# M624X.net
KiCad netlist of a schematic drawn in EAGLE
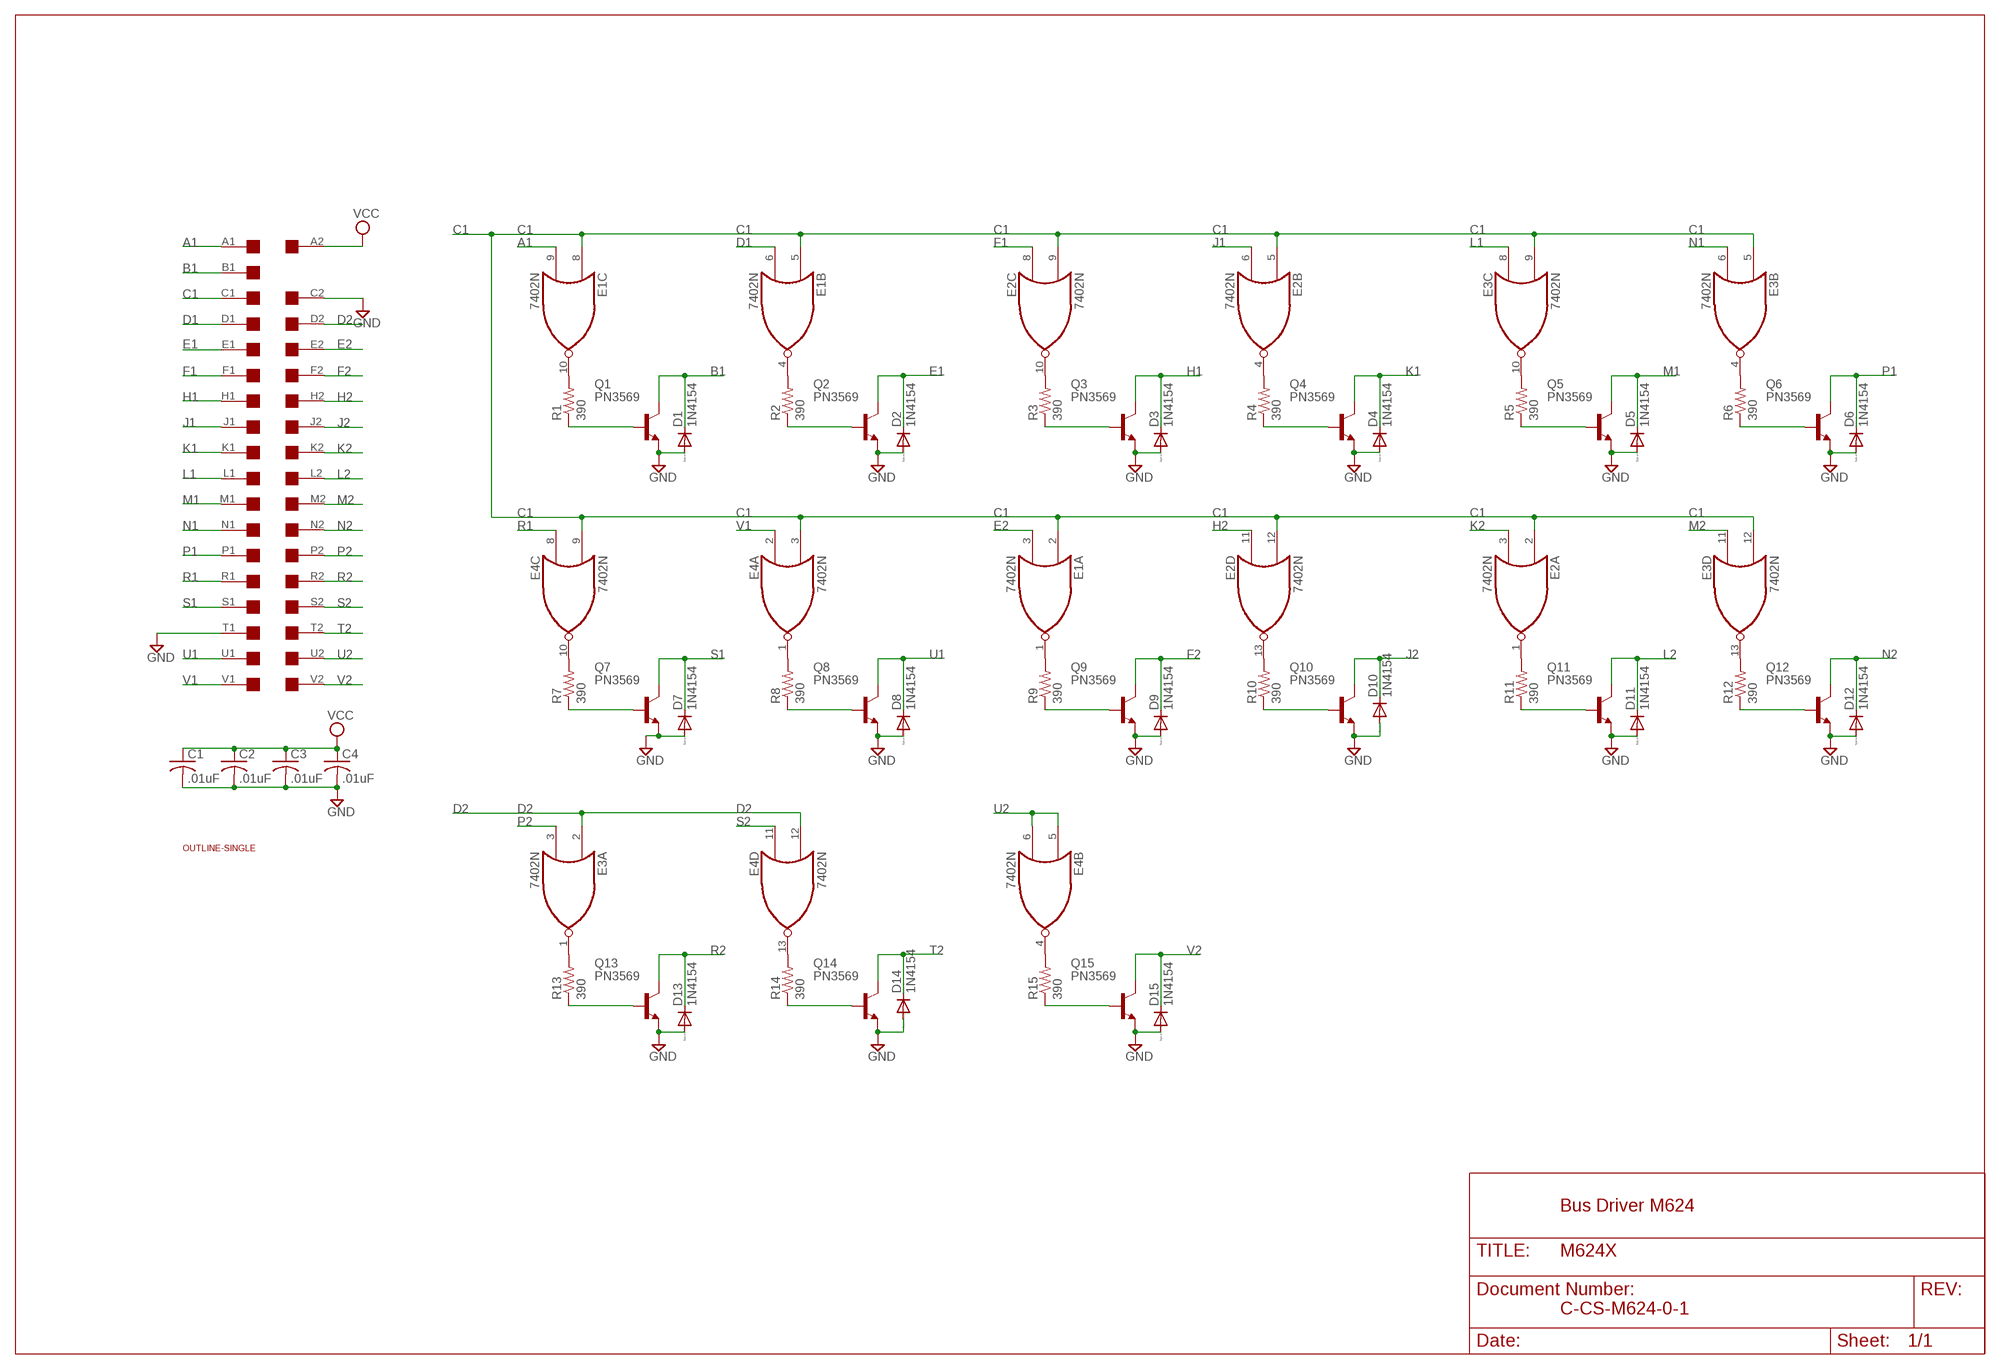
[diagram p0: schematic, sheet 1]

(export (version "E")
  (design (tool "Eeschema 10.0.6"))
  (components
    (comp (ref "C1")
      (value ".01uF")
      (footprint "eagle-import:C050-025X075")
      (libsource (lib "eagle-import") (part "C-US050-025X075"))
    )
    (comp (ref "C2")
      (value ".01uF")
      (footprint "eagle-import:C050-025X075")
      (libsource (lib "eagle-import") (part "C-US050-025X075"))
    )
    (comp (ref "C3")
      (value ".01uF")
      (footprint "eagle-import:C050-025X075")
      (libsource (lib "eagle-import") (part "C-US050-025X075"))
    )
    (comp (ref "C4")
      (value ".01uF")
      (footprint "eagle-import:C050-025X075")
      (libsource (lib "eagle-import") (part "C-US050-025X075"))
    )
    (comp (ref "D1")
      (value "1N4154")
      (footprint "eagle-import:DO35-10")
      (libsource (lib "eagle-import") (part "1N4148DO35-10"))
    )
    (comp (ref "D2")
      (value "1N4154")
      (footprint "eagle-import:DO35-10")
      (libsource (lib "eagle-import") (part "1N4148DO35-10"))
    )
    (comp (ref "D3")
      (value "1N4154")
      (footprint "eagle-import:DO35-10")
      (libsource (lib "eagle-import") (part "1N4148DO35-10"))
    )
    (comp (ref "D4")
      (value "1N4154")
      (footprint "eagle-import:DO35-10")
      (libsource (lib "eagle-import") (part "1N4148DO35-10"))
    )
    (comp (ref "D5")
      (value "1N4154")
      (footprint "eagle-import:DO35-10")
      (libsource (lib "eagle-import") (part "1N4148DO35-10"))
    )
    (comp (ref "D6")
      (value "1N4154")
      (footprint "eagle-import:DO35-10")
      (libsource (lib "eagle-import") (part "1N4148DO35-10"))
    )
    (comp (ref "D7")
      (value "1N4154")
      (footprint "eagle-import:DO35-10")
      (libsource (lib "eagle-import") (part "1N4148DO35-10"))
    )
    (comp (ref "D8")
      (value "1N4154")
      (footprint "eagle-import:DO35-10")
      (libsource (lib "eagle-import") (part "1N4148DO35-10"))
    )
    (comp (ref "D9")
      (value "1N4154")
      (footprint "eagle-import:DO35-10")
      (libsource (lib "eagle-import") (part "1N4148DO35-10"))
    )
    (comp (ref "D10")
      (value "1N4154")
      (footprint "eagle-import:DO35-10")
      (libsource (lib "eagle-import") (part "1N4148DO35-10"))
    )
    (comp (ref "D11")
      (value "1N4154")
      (footprint "eagle-import:DO35-10")
      (libsource (lib "eagle-import") (part "1N4148DO35-10"))
    )
    (comp (ref "D12")
      (value "1N4154")
      (footprint "eagle-import:DO35-10")
      (libsource (lib "eagle-import") (part "1N4148DO35-10"))
    )
    (comp (ref "D13")
      (value "1N4154")
      (footprint "eagle-import:DO35-10")
      (libsource (lib "eagle-import") (part "1N4148DO35-10"))
    )
    (comp (ref "D14")
      (value "1N4154")
      (footprint "eagle-import:DO35-10")
      (libsource (lib "eagle-import") (part "1N4148DO35-10"))
    )
    (comp (ref "D15")
      (value "1N4154")
      (footprint "eagle-import:DO35-10")
      (libsource (lib "eagle-import") (part "1N4148DO35-10"))
    )
    (comp (ref "E1")
      (value "7402N")
      (footprint "eagle-import:DIL14")
      (libsource (lib "eagle-import") (part "7402N"))
    )
    (comp (ref "E2")
      (value "7402N")
      (footprint "eagle-import:DIL14")
      (libsource (lib "eagle-import") (part "7402N"))
    )
    (comp (ref "E3")
      (value "7402N")
      (footprint "eagle-import:DIL14")
      (libsource (lib "eagle-import") (part "7402N"))
    )
    (comp (ref "E4")
      (value "7402N")
      (footprint "eagle-import:DIL14")
      (libsource (lib "eagle-import") (part "7402N"))
    )
    (comp (ref "Q1")
      (value "PN3569")
      (footprint "eagle-import:TO39")
      (libsource (lib "eagle-import") (part "-NPN-TO39-EBC2N1613"))
    )
    (comp (ref "Q2")
      (value "PN3569")
      (footprint "eagle-import:TO39")
      (libsource (lib "eagle-import") (part "-NPN-TO39-EBC2N1613"))
    )
    (comp (ref "Q3")
      (value "PN3569")
      (footprint "eagle-import:TO39")
      (libsource (lib "eagle-import") (part "-NPN-TO39-EBC2N1613"))
    )
    (comp (ref "Q4")
      (value "PN3569")
      (footprint "eagle-import:TO39")
      (libsource (lib "eagle-import") (part "-NPN-TO39-EBC2N1613"))
    )
    (comp (ref "Q5")
      (value "PN3569")
      (footprint "eagle-import:TO39")
      (libsource (lib "eagle-import") (part "-NPN-TO39-EBC2N1613"))
    )
    (comp (ref "Q6")
      (value "PN3569")
      (footprint "eagle-import:TO39")
      (libsource (lib "eagle-import") (part "-NPN-TO39-EBC2N1613"))
    )
    (comp (ref "Q7")
      (value "PN3569")
      (footprint "eagle-import:TO39")
      (libsource (lib "eagle-import") (part "-NPN-TO39-EBC2N1613"))
    )
    (comp (ref "Q8")
      (value "PN3569")
      (footprint "eagle-import:TO39")
      (libsource (lib "eagle-import") (part "-NPN-TO39-EBC2N1613"))
    )
    (comp (ref "Q9")
      (value "PN3569")
      (footprint "eagle-import:TO39")
      (libsource (lib "eagle-import") (part "-NPN-TO39-EBC2N1613"))
    )
    (comp (ref "Q10")
      (value "PN3569")
      (footprint "eagle-import:TO39")
      (libsource (lib "eagle-import") (part "-NPN-TO39-EBC2N1613"))
    )
    (comp (ref "Q11")
      (value "PN3569")
      (footprint "eagle-import:TO39")
      (libsource (lib "eagle-import") (part "-NPN-TO39-EBC2N1613"))
    )
    (comp (ref "Q12")
      (value "PN3569")
      (footprint "eagle-import:TO39")
      (libsource (lib "eagle-import") (part "-NPN-TO39-EBC2N1613"))
    )
    (comp (ref "Q13")
      (value "PN3569")
      (footprint "eagle-import:TO39")
      (libsource (lib "eagle-import") (part "-NPN-TO39-EBC2N1613"))
    )
    (comp (ref "Q14")
      (value "PN3569")
      (footprint "eagle-import:TO39")
      (libsource (lib "eagle-import") (part "-NPN-TO39-EBC2N1613"))
    )
    (comp (ref "Q15")
      (value "PN3569")
      (footprint "eagle-import:TO39")
      (libsource (lib "eagle-import") (part "-NPN-TO39-EBC2N1613"))
    )
    (comp (ref "R1")
      (value "390")
      (footprint "eagle-import:0207_10")
      (libsource (lib "eagle-import") (part "R-US_0207/10"))
    )
    (comp (ref "R2")
      (value "390")
      (footprint "eagle-import:0207_10")
      (libsource (lib "eagle-import") (part "R-US_0207/10"))
    )
    (comp (ref "R3")
      (value "390")
      (footprint "eagle-import:0207_10")
      (libsource (lib "eagle-import") (part "R-US_0207/10"))
    )
    (comp (ref "R4")
      (value "390")
      (footprint "eagle-import:0207_10")
      (libsource (lib "eagle-import") (part "R-US_0207/10"))
    )
    (comp (ref "R5")
      (value "390")
      (footprint "eagle-import:0207_10")
      (libsource (lib "eagle-import") (part "R-US_0207/10"))
    )
    (comp (ref "R6")
      (value "390")
      (footprint "eagle-import:0207_10")
      (libsource (lib "eagle-import") (part "R-US_0207/10"))
    )
    (comp (ref "R7")
      (value "390")
      (footprint "eagle-import:0207_10")
      (libsource (lib "eagle-import") (part "R-US_0207/10"))
    )
    (comp (ref "R8")
      (value "390")
      (footprint "eagle-import:0207_10")
      (libsource (lib "eagle-import") (part "R-US_0207/10"))
    )
    (comp (ref "R9")
      (value "390")
      (footprint "eagle-import:0207_10")
      (libsource (lib "eagle-import") (part "R-US_0207/10"))
    )
    (comp (ref "R10")
      (value "390")
      (footprint "eagle-import:0207_10")
      (libsource (lib "eagle-import") (part "R-US_0207/10"))
    )
    (comp (ref "R11")
      (value "390")
      (footprint "eagle-import:0207_10")
      (libsource (lib "eagle-import") (part "R-US_0207/10"))
    )
    (comp (ref "R12")
      (value "390")
      (footprint "eagle-import:0207_10")
      (libsource (lib "eagle-import") (part "R-US_0207/10"))
    )
    (comp (ref "R13")
      (value "390")
      (footprint "eagle-import:0207_10")
      (libsource (lib "eagle-import") (part "R-US_0207/10"))
    )
    (comp (ref "R14")
      (value "390")
      (footprint "eagle-import:0207_10")
      (libsource (lib "eagle-import") (part "R-US_0207/10"))
    )
    (comp (ref "R15")
      (value "390")
      (footprint "eagle-import:0207_10")
      (libsource (lib "eagle-import") (part "R-US_0207/10"))
    )
    (comp (ref "U$1")
      (value "OUTLINE-SINGLE")
      (footprint "eagle-import:SINGLE")
      (libsource (lib "eagle-import") (part "OUTLINE-SINGLE"))
    )
    (comp (ref "U$4")
      (value "SINGLE")
      (footprint "eagle-import:EDGE-CON2")
      (libsource (lib "eagle-import") (part "SINGLE"))
    )
  )
  (nets
    (net (code "1") (name "/A1") (class "Default")
      (node (ref "E1") (pin "9") (pinfunction "I1_9") (pintype "input"))
      (node (ref "U$4") (pin "A1") (pinfunction "1_A1") (pintype "bidirectional"))
    )
    (net (code "2") (name "/B1") (class "Default")
      (node (ref "D1") (pin "C") (pinfunction "C_C") (pintype "passive"))
      (node (ref "Q1") (pin "3") (pinfunction "C_3") (pintype "passive"))
      (node (ref "U$4") (pin "B1") (pinfunction "1_B1") (pintype "bidirectional"))
    )
    (net (code "3") (name "/C1") (class "Default")
      (node (ref "E1") (pin "2") (pinfunction "I0_2") (pintype "input"))
      (node (ref "E1") (pin "5") (pinfunction "I0_5") (pintype "input"))
      (node (ref "E1") (pin "8") (pinfunction "I0_8") (pintype "input"))
      (node (ref "E2") (pin "12") (pinfunction "I1_12") (pintype "input"))
      (node (ref "E2") (pin "2") (pinfunction "I0_2") (pintype "input"))
      (node (ref "E2") (pin "5") (pinfunction "I0_5") (pintype "input"))
      (node (ref "E2") (pin "9") (pinfunction "I1_9") (pintype "input"))
      (node (ref "E3") (pin "12") (pinfunction "I1_12") (pintype "input"))
      (node (ref "E3") (pin "5") (pinfunction "I0_5") (pintype "input"))
      (node (ref "E3") (pin "9") (pinfunction "I1_9") (pintype "input"))
      (node (ref "E4") (pin "3") (pinfunction "I1_3") (pintype "input"))
      (node (ref "E4") (pin "9") (pinfunction "I1_9") (pintype "input"))
      (node (ref "U$4") (pin "C1") (pinfunction "1_C1") (pintype "bidirectional"))
    )
    (net (code "4") (name "/D1") (class "Default")
      (node (ref "E1") (pin "6") (pinfunction "I1_6") (pintype "input"))
      (node (ref "U$4") (pin "D1") (pinfunction "1_D1") (pintype "bidirectional"))
    )
    (net (code "5") (name "/D2") (class "Default")
      (node (ref "E3") (pin "2") (pinfunction "I0_2") (pintype "input"))
      (node (ref "E4") (pin "12") (pinfunction "I1_12") (pintype "input"))
      (node (ref "U$4") (pin "D2") (pinfunction "1_D2") (pintype "bidirectional"))
    )
    (net (code "6") (name "/E1") (class "Default")
      (node (ref "D2") (pin "C") (pinfunction "C_C") (pintype "passive"))
      (node (ref "Q2") (pin "3") (pinfunction "C_3") (pintype "passive"))
      (node (ref "U$4") (pin "E1") (pinfunction "1_E1") (pintype "bidirectional"))
    )
    (net (code "7") (name "/E2") (class "Default")
      (node (ref "E1") (pin "3") (pinfunction "I1_3") (pintype "input"))
      (node (ref "U$4") (pin "E2") (pinfunction "1_E2") (pintype "bidirectional"))
    )
    (net (code "8") (name "/F1") (class "Default")
      (node (ref "E2") (pin "8") (pinfunction "I0_8") (pintype "input"))
      (node (ref "U$4") (pin "F1") (pinfunction "1_F1") (pintype "bidirectional"))
    )
    (net (code "9") (name "/F2") (class "Default")
      (node (ref "D9") (pin "C") (pinfunction "C_C") (pintype "passive"))
      (node (ref "Q9") (pin "3") (pinfunction "C_3") (pintype "passive"))
      (node (ref "U$4") (pin "F2") (pinfunction "1_F2") (pintype "bidirectional"))
    )
    (net (code "10") (name "/H1") (class "Default")
      (node (ref "D3") (pin "C") (pinfunction "C_C") (pintype "passive"))
      (node (ref "Q3") (pin "3") (pinfunction "C_3") (pintype "passive"))
      (node (ref "U$4") (pin "H1") (pinfunction "1_H1") (pintype "bidirectional"))
    )
    (net (code "11") (name "/H2") (class "Default")
      (node (ref "E2") (pin "11") (pinfunction "I0_11") (pintype "input"))
      (node (ref "U$4") (pin "H2") (pinfunction "1_H2") (pintype "bidirectional"))
    )
    (net (code "12") (name "/J1") (class "Default")
      (node (ref "E2") (pin "6") (pinfunction "I1_6") (pintype "input"))
      (node (ref "U$4") (pin "J1") (pinfunction "1_J1") (pintype "bidirectional"))
    )
    (net (code "13") (name "/J2") (class "Default")
      (node (ref "D10") (pin "C") (pinfunction "C_C") (pintype "passive"))
      (node (ref "Q10") (pin "3") (pinfunction "C_3") (pintype "passive"))
      (node (ref "U$4") (pin "J2") (pinfunction "1_J2") (pintype "bidirectional"))
    )
    (net (code "14") (name "/K1") (class "Default")
      (node (ref "D4") (pin "C") (pinfunction "C_C") (pintype "passive"))
      (node (ref "Q4") (pin "3") (pinfunction "C_3") (pintype "passive"))
      (node (ref "U$4") (pin "K1") (pinfunction "1_K1") (pintype "bidirectional"))
    )
    (net (code "15") (name "/K2") (class "Default")
      (node (ref "E2") (pin "3") (pinfunction "I1_3") (pintype "input"))
      (node (ref "U$4") (pin "K2") (pinfunction "1_K2") (pintype "bidirectional"))
    )
    (net (code "16") (name "/L1") (class "Default")
      (node (ref "E3") (pin "8") (pinfunction "I0_8") (pintype "input"))
      (node (ref "U$4") (pin "L1") (pinfunction "1_L1") (pintype "bidirectional"))
    )
    (net (code "17") (name "/L2") (class "Default")
      (node (ref "D11") (pin "C") (pinfunction "C_C") (pintype "passive"))
      (node (ref "Q11") (pin "3") (pinfunction "C_3") (pintype "passive"))
      (node (ref "U$4") (pin "L2") (pinfunction "1_L2") (pintype "bidirectional"))
    )
    (net (code "18") (name "/M1") (class "Default")
      (node (ref "D5") (pin "C") (pinfunction "C_C") (pintype "passive"))
      (node (ref "Q5") (pin "3") (pinfunction "C_3") (pintype "passive"))
      (node (ref "U$4") (pin "M1") (pinfunction "1_M1") (pintype "bidirectional"))
    )
    (net (code "19") (name "/M2") (class "Default")
      (node (ref "E3") (pin "11") (pinfunction "I0_11") (pintype "input"))
      (node (ref "U$4") (pin "M2") (pinfunction "1_M2") (pintype "bidirectional"))
    )
    (net (code "20") (name "/N1") (class "Default")
      (node (ref "E3") (pin "6") (pinfunction "I1_6") (pintype "input"))
      (node (ref "U$4") (pin "N1") (pinfunction "1_N1") (pintype "bidirectional"))
    )
    (net (code "21") (name "/N2") (class "Default")
      (node (ref "D12") (pin "C") (pinfunction "C_C") (pintype "passive"))
      (node (ref "Q12") (pin "3") (pinfunction "C_3") (pintype "passive"))
      (node (ref "U$4") (pin "N2") (pinfunction "1_N2") (pintype "bidirectional"))
    )
    (net (code "22") (name "/P1") (class "Default")
      (node (ref "D6") (pin "C") (pinfunction "C_C") (pintype "passive"))
      (node (ref "Q6") (pin "3") (pinfunction "C_3") (pintype "passive"))
      (node (ref "U$4") (pin "P1") (pinfunction "1_P1") (pintype "bidirectional"))
    )
    (net (code "23") (name "/P2") (class "Default")
      (node (ref "E3") (pin "3") (pinfunction "I1_3") (pintype "input"))
      (node (ref "U$4") (pin "P2") (pinfunction "1_P2") (pintype "bidirectional"))
    )
    (net (code "24") (name "/R1") (class "Default")
      (node (ref "E4") (pin "8") (pinfunction "I0_8") (pintype "input"))
      (node (ref "U$4") (pin "R1") (pinfunction "1_R1") (pintype "bidirectional"))
    )
    (net (code "25") (name "/R2") (class "Default")
      (node (ref "D13") (pin "C") (pinfunction "C_C") (pintype "passive"))
      (node (ref "Q13") (pin "3") (pinfunction "C_3") (pintype "passive"))
      (node (ref "U$4") (pin "R2") (pinfunction "1_R2") (pintype "bidirectional"))
    )
    (net (code "26") (name "/S1") (class "Default")
      (node (ref "D7") (pin "C") (pinfunction "C_C") (pintype "passive"))
      (node (ref "Q7") (pin "3") (pinfunction "C_3") (pintype "passive"))
      (node (ref "U$4") (pin "S1") (pinfunction "1_S1") (pintype "bidirectional"))
    )
    (net (code "27") (name "/S2") (class "Default")
      (node (ref "E4") (pin "11") (pinfunction "I0_11") (pintype "input"))
      (node (ref "U$4") (pin "S2") (pinfunction "1_S2") (pintype "bidirectional"))
    )
    (net (code "28") (name "/T2") (class "Default")
      (node (ref "D14") (pin "C") (pinfunction "C_C") (pintype "passive"))
      (node (ref "Q14") (pin "3") (pinfunction "C_3") (pintype "passive"))
      (node (ref "U$4") (pin "T2") (pinfunction "1_T2") (pintype "bidirectional"))
    )
    (net (code "29") (name "/U1") (class "Default")
      (node (ref "D8") (pin "C") (pinfunction "C_C") (pintype "passive"))
      (node (ref "Q8") (pin "3") (pinfunction "C_3") (pintype "passive"))
      (node (ref "U$4") (pin "U1") (pinfunction "1_U1") (pintype "bidirectional"))
    )
    (net (code "30") (name "/U2") (class "Default")
      (node (ref "E4") (pin "5") (pinfunction "I0_5") (pintype "input"))
      (node (ref "E4") (pin "6") (pinfunction "I1_6") (pintype "input"))
      (node (ref "U$4") (pin "U2") (pinfunction "1_U2") (pintype "bidirectional"))
    )
    (net (code "31") (name "/V1") (class "Default")
      (node (ref "E4") (pin "2") (pinfunction "I0_2") (pintype "input"))
      (node (ref "U$4") (pin "V1") (pinfunction "1_V1") (pintype "bidirectional"))
    )
    (net (code "32") (name "/V2") (class "Default")
      (node (ref "D15") (pin "C") (pinfunction "C_C") (pintype "passive"))
      (node (ref "Q15") (pin "3") (pinfunction "C_3") (pintype "passive"))
      (node (ref "U$4") (pin "V2") (pinfunction "1_V2") (pintype "bidirectional"))
    )
    (net (code "33") (name "GND") (class "Default")
      (node (ref "C1") (pin "2") (pinfunction "2_2") (pintype "passive"))
      (node (ref "C2") (pin "2") (pinfunction "2_2") (pintype "passive"))
      (node (ref "C3") (pin "2") (pinfunction "2_2") (pintype "passive"))
      (node (ref "C4") (pin "2") (pinfunction "2_2") (pintype "passive"))
      (node (ref "D1") (pin "A") (pinfunction "A_A") (pintype "passive"))
      (node (ref "D10") (pin "A") (pinfunction "A_A") (pintype "passive"))
      (node (ref "D11") (pin "A") (pinfunction "A_A") (pintype "passive"))
      (node (ref "D12") (pin "A") (pinfunction "A_A") (pintype "passive"))
      (node (ref "D13") (pin "A") (pinfunction "A_A") (pintype "passive"))
      (node (ref "D14") (pin "A") (pinfunction "A_A") (pintype "passive"))
      (node (ref "D15") (pin "A") (pinfunction "A_A") (pintype "passive"))
      (node (ref "D2") (pin "A") (pinfunction "A_A") (pintype "passive"))
      (node (ref "D3") (pin "A") (pinfunction "A_A") (pintype "passive"))
      (node (ref "D4") (pin "A") (pinfunction "A_A") (pintype "passive"))
      (node (ref "D5") (pin "A") (pinfunction "A_A") (pintype "passive"))
      (node (ref "D6") (pin "A") (pinfunction "A_A") (pintype "passive"))
      (node (ref "D7") (pin "A") (pinfunction "A_A") (pintype "passive"))
      (node (ref "D8") (pin "A") (pinfunction "A_A") (pintype "passive"))
      (node (ref "D9") (pin "A") (pinfunction "A_A") (pintype "passive"))
      (node (ref "Q1") (pin "1") (pinfunction "E_1") (pintype "passive"))
      (node (ref "Q10") (pin "1") (pinfunction "E_1") (pintype "passive"))
      (node (ref "Q11") (pin "1") (pinfunction "E_1") (pintype "passive"))
      (node (ref "Q12") (pin "1") (pinfunction "E_1") (pintype "passive"))
      (node (ref "Q13") (pin "1") (pinfunction "E_1") (pintype "passive"))
      (node (ref "Q14") (pin "1") (pinfunction "E_1") (pintype "passive"))
      (node (ref "Q15") (pin "1") (pinfunction "E_1") (pintype "passive"))
      (node (ref "Q2") (pin "1") (pinfunction "E_1") (pintype "passive"))
      (node (ref "Q3") (pin "1") (pinfunction "E_1") (pintype "passive"))
      (node (ref "Q4") (pin "1") (pinfunction "E_1") (pintype "passive"))
      (node (ref "Q5") (pin "1") (pinfunction "E_1") (pintype "passive"))
      (node (ref "Q6") (pin "1") (pinfunction "E_1") (pintype "passive"))
      (node (ref "Q7") (pin "1") (pinfunction "E_1") (pintype "passive"))
      (node (ref "Q8") (pin "1") (pinfunction "E_1") (pintype "passive"))
      (node (ref "Q9") (pin "1") (pinfunction "E_1") (pintype "passive"))
      (node (ref "U$4") (pin "C2") (pinfunction "1_C2") (pintype "bidirectional"))
      (node (ref "U$4") (pin "T1") (pinfunction "1_T1") (pintype "bidirectional"))
    )
    (net (code "34") (name "Net-(E1A-O)") (class "Default")
      (node (ref "E1") (pin "1") (pinfunction "O_1") (pintype "output"))
      (node (ref "R9") (pin "2") (pinfunction "2_2") (pintype "passive"))
    )
    (net (code "35") (name "Net-(E1B-O)") (class "Default")
      (node (ref "E1") (pin "4") (pinfunction "O_4") (pintype "output"))
      (node (ref "R2") (pin "2") (pinfunction "2_2") (pintype "passive"))
    )
    (net (code "36") (name "Net-(E1C-O)") (class "Default")
      (node (ref "E1") (pin "10") (pinfunction "O_10") (pintype "output"))
      (node (ref "R1") (pin "2") (pinfunction "2_2") (pintype "passive"))
    )
    (net (code "37") (name "Net-(E2A-O)") (class "Default")
      (node (ref "E2") (pin "1") (pinfunction "O_1") (pintype "output"))
      (node (ref "R11") (pin "2") (pinfunction "2_2") (pintype "passive"))
    )
    (net (code "38") (name "Net-(E2B-O)") (class "Default")
      (node (ref "E2") (pin "4") (pinfunction "O_4") (pintype "output"))
      (node (ref "R4") (pin "2") (pinfunction "2_2") (pintype "passive"))
    )
    (net (code "39") (name "Net-(E2C-O)") (class "Default")
      (node (ref "E2") (pin "10") (pinfunction "O_10") (pintype "output"))
      (node (ref "R3") (pin "2") (pinfunction "2_2") (pintype "passive"))
    )
    (net (code "40") (name "Net-(E2D-O)") (class "Default")
      (node (ref "E2") (pin "13") (pinfunction "O_13") (pintype "output"))
      (node (ref "R10") (pin "2") (pinfunction "2_2") (pintype "passive"))
    )
    (net (code "41") (name "Net-(E3A-O)") (class "Default")
      (node (ref "E3") (pin "1") (pinfunction "O_1") (pintype "output"))
      (node (ref "R13") (pin "2") (pinfunction "2_2") (pintype "passive"))
    )
    (net (code "42") (name "Net-(E3B-O)") (class "Default")
      (node (ref "E3") (pin "4") (pinfunction "O_4") (pintype "output"))
      (node (ref "R6") (pin "2") (pinfunction "2_2") (pintype "passive"))
    )
    (net (code "43") (name "Net-(E3C-O)") (class "Default")
      (node (ref "E3") (pin "10") (pinfunction "O_10") (pintype "output"))
      (node (ref "R5") (pin "2") (pinfunction "2_2") (pintype "passive"))
    )
    (net (code "44") (name "Net-(E3D-O)") (class "Default")
      (node (ref "E3") (pin "13") (pinfunction "O_13") (pintype "output"))
      (node (ref "R12") (pin "2") (pinfunction "2_2") (pintype "passive"))
    )
    (net (code "45") (name "Net-(E4A-O)") (class "Default")
      (node (ref "E4") (pin "1") (pinfunction "O_1") (pintype "output"))
      (node (ref "R8") (pin "2") (pinfunction "2_2") (pintype "passive"))
    )
    (net (code "46") (name "Net-(E4B-O)") (class "Default")
      (node (ref "E4") (pin "4") (pinfunction "O_4") (pintype "output"))
      (node (ref "R15") (pin "2") (pinfunction "2_2") (pintype "passive"))
    )
    (net (code "47") (name "Net-(E4C-O)") (class "Default")
      (node (ref "E4") (pin "10") (pinfunction "O_10") (pintype "output"))
      (node (ref "R7") (pin "2") (pinfunction "2_2") (pintype "passive"))
    )
    (net (code "48") (name "Net-(E4D-O)") (class "Default")
      (node (ref "E4") (pin "13") (pinfunction "O_13") (pintype "output"))
      (node (ref "R14") (pin "2") (pinfunction "2_2") (pintype "passive"))
    )
    (net (code "49") (name "Net-(Q1-B)") (class "Default")
      (node (ref "Q1") (pin "2") (pinfunction "B_2") (pintype "passive"))
      (node (ref "R1") (pin "1") (pinfunction "1_1") (pintype "passive"))
    )
    (net (code "50") (name "Net-(Q2-B)") (class "Default")
      (node (ref "Q2") (pin "2") (pinfunction "B_2") (pintype "passive"))
      (node (ref "R2") (pin "1") (pinfunction "1_1") (pintype "passive"))
    )
    (net (code "51") (name "Net-(Q3-B)") (class "Default")
      (node (ref "Q3") (pin "2") (pinfunction "B_2") (pintype "passive"))
      (node (ref "R3") (pin "1") (pinfunction "1_1") (pintype "passive"))
    )
    (net (code "52") (name "Net-(Q4-B)") (class "Default")
      (node (ref "Q4") (pin "2") (pinfunction "B_2") (pintype "passive"))
      (node (ref "R4") (pin "1") (pinfunction "1_1") (pintype "passive"))
    )
    (net (code "53") (name "Net-(Q5-B)") (class "Default")
      (node (ref "Q5") (pin "2") (pinfunction "B_2") (pintype "passive"))
      (node (ref "R5") (pin "1") (pinfunction "1_1") (pintype "passive"))
    )
    (net (code "54") (name "Net-(Q6-B)") (class "Default")
      (node (ref "Q6") (pin "2") (pinfunction "B_2") (pintype "passive"))
      (node (ref "R6") (pin "1") (pinfunction "1_1") (pintype "passive"))
    )
    (net (code "55") (name "Net-(Q7-B)") (class "Default")
      (node (ref "Q7") (pin "2") (pinfunction "B_2") (pintype "passive"))
      (node (ref "R7") (pin "1") (pinfunction "1_1") (pintype "passive"))
    )
    (net (code "56") (name "Net-(Q8-B)") (class "Default")
      (node (ref "Q8") (pin "2") (pinfunction "B_2") (pintype "passive"))
      (node (ref "R8") (pin "1") (pinfunction "1_1") (pintype "passive"))
    )
    (net (code "57") (name "Net-(Q9-B)") (class "Default")
      (node (ref "Q9") (pin "2") (pinfunction "B_2") (pintype "passive"))
      (node (ref "R9") (pin "1") (pinfunction "1_1") (pintype "passive"))
    )
    (net (code "58") (name "Net-(Q10-B)") (class "Default")
      (node (ref "Q10") (pin "2") (pinfunction "B_2") (pintype "passive"))
      (node (ref "R10") (pin "1") (pinfunction "1_1") (pintype "passive"))
    )
    (net (code "59") (name "Net-(Q11-B)") (class "Default")
      (node (ref "Q11") (pin "2") (pinfunction "B_2") (pintype "passive"))
      (node (ref "R11") (pin "1") (pinfunction "1_1") (pintype "passive"))
    )
    (net (code "60") (name "Net-(Q12-B)") (class "Default")
      (node (ref "Q12") (pin "2") (pinfunction "B_2") (pintype "passive"))
      (node (ref "R12") (pin "1") (pinfunction "1_1") (pintype "passive"))
    )
    (net (code "61") (name "Net-(Q13-B)") (class "Default")
      (node (ref "Q13") (pin "2") (pinfunction "B_2") (pintype "passive"))
      (node (ref "R13") (pin "1") (pinfunction "1_1") (pintype "passive"))
    )
    (net (code "62") (name "Net-(Q14-B)") (class "Default")
      (node (ref "Q14") (pin "2") (pinfunction "B_2") (pintype "passive"))
      (node (ref "R14") (pin "1") (pinfunction "1_1") (pintype "passive"))
    )
    (net (code "63") (name "Net-(Q15-B)") (class "Default")
      (node (ref "Q15") (pin "2") (pinfunction "B_2") (pintype "passive"))
      (node (ref "R15") (pin "1") (pinfunction "1_1") (pintype "passive"))
    )
    (net (code "64") (name "VCC") (class "Default")
      (node (ref "C1") (pin "1") (pinfunction "1_1") (pintype "passive"))
      (node (ref "C2") (pin "1") (pinfunction "1_1") (pintype "passive"))
      (node (ref "C3") (pin "1") (pinfunction "1_1") (pintype "passive"))
      (node (ref "C4") (pin "1") (pinfunction "1_1") (pintype "passive"))
      (node (ref "U$4") (pin "A2") (pinfunction "1_A2") (pintype "bidirectional"))
    )
  )
)
